# W5500_EVB_V1_0.net
KiCad netlist of a schematic drawn in EAGLE
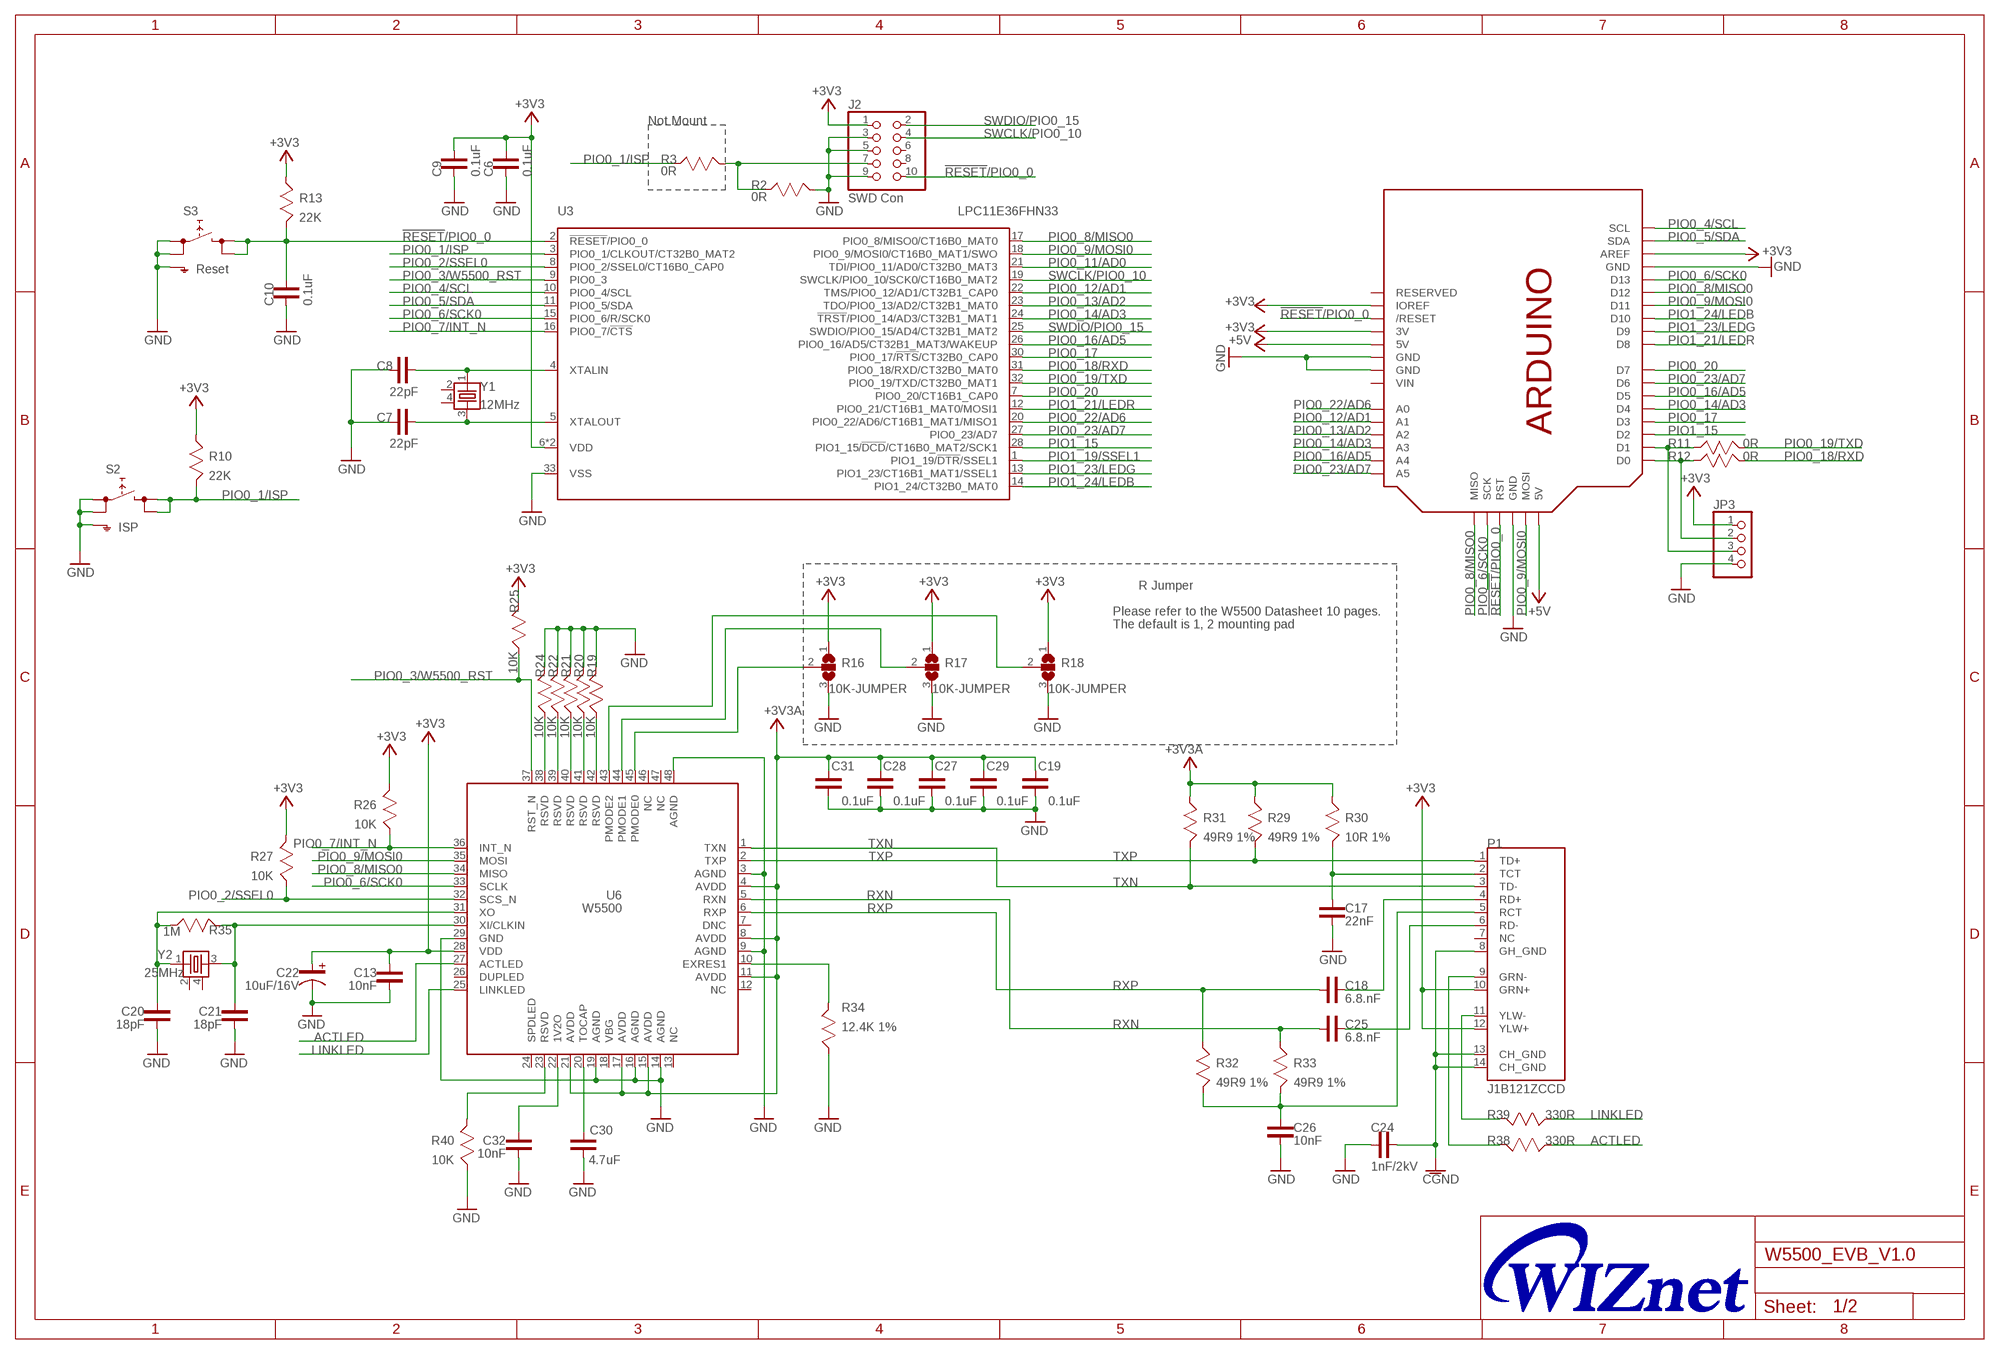
[diagram p0: schematic, sheet 1]
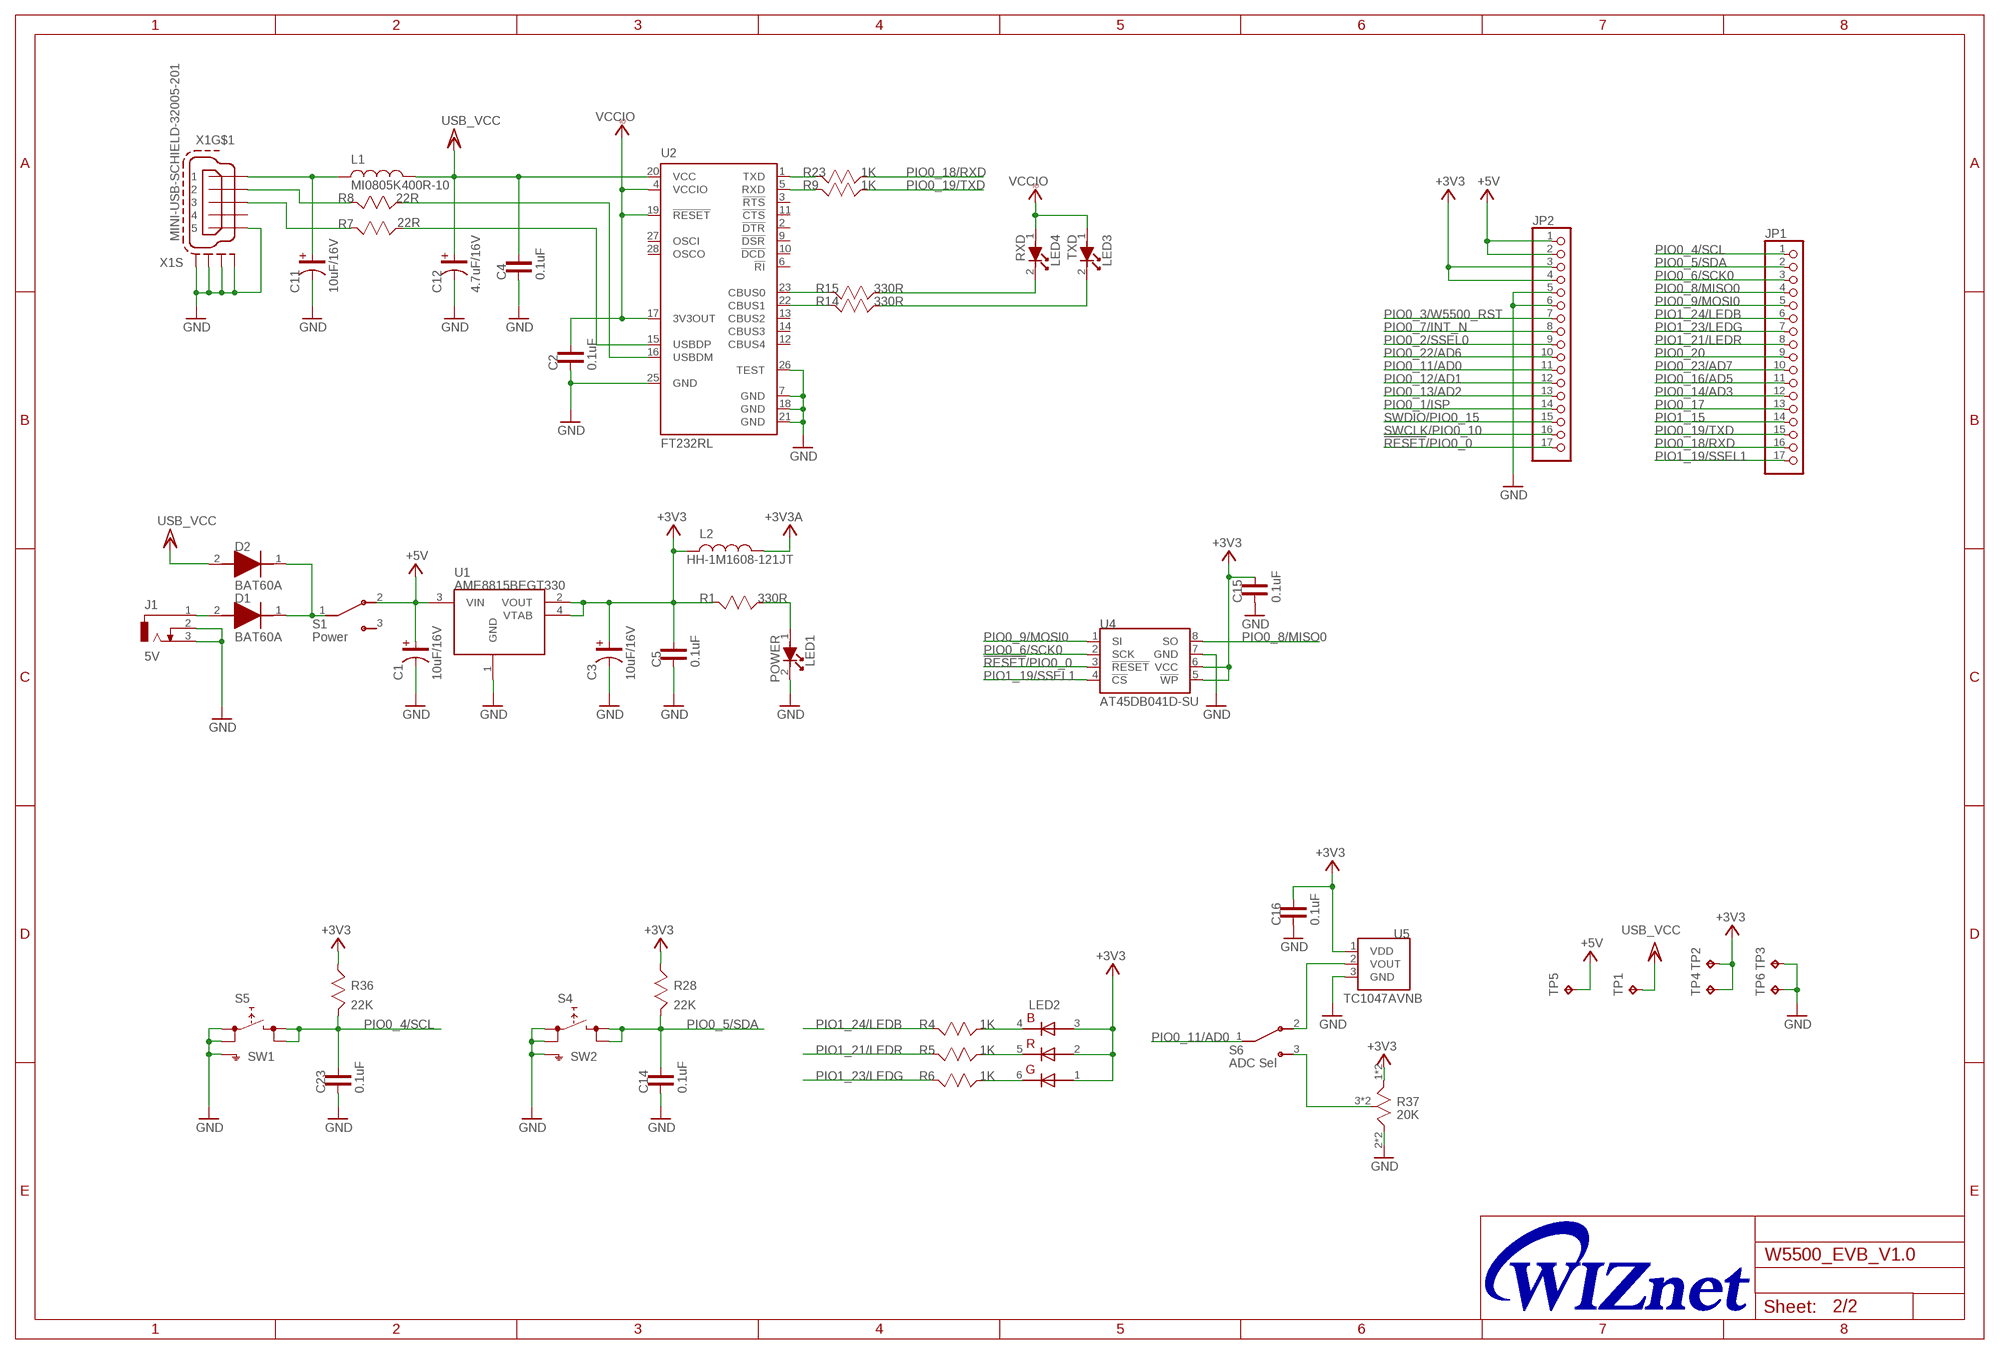
[diagram p1: schematic, sheet 2]

(export (version "E")
  (design (tool "Eeschema 10.0.6"))
  (components
    (comp (ref "$$U$3")
      (value "ARDUINO_R3_ICSP")
      (footprint "eagle-import:ARDUINOR3_ICSP")
      (libsource (lib "eagle-import") (part "ARDUINO_R3_ICSP"))
    )
    (comp (ref "C6")
      (value "0.1uF")
      (footprint "eagle-import:C-1608")
      (libsource (lib "eagle-import") (part "C-1608"))
    )
    (comp (ref "C7")
      (value "22pF")
      (footprint "eagle-import:C-1608")
      (libsource (lib "eagle-import") (part "C-1608"))
    )
    (comp (ref "C8")
      (value "22pF")
      (footprint "eagle-import:C-1608")
      (libsource (lib "eagle-import") (part "C-1608"))
    )
    (comp (ref "C9")
      (value "0.1uF")
      (footprint "eagle-import:C-1608")
      (libsource (lib "eagle-import") (part "C-1608"))
    )
    (comp (ref "C10")
      (value "0.1uF")
      (footprint "eagle-import:C-1608")
      (libsource (lib "eagle-import") (part "C-1608"))
    )
    (comp (ref "C13")
      (value "10nF")
      (footprint "eagle-import:C-1608")
      (libsource (lib "eagle-import") (part "C-1608"))
    )
    (comp (ref "C17")
      (value "22nF")
      (footprint "eagle-import:C-1608")
      (libsource (lib "eagle-import") (part "C-1608"))
    )
    (comp (ref "C18")
      (value "6.8.nF")
      (footprint "eagle-import:C-1608")
      (libsource (lib "eagle-import") (part "C-1608"))
    )
    (comp (ref "C19")
      (value "0.1uF")
      (footprint "eagle-import:C-1608")
      (libsource (lib "eagle-import") (part "C-1608"))
    )
    (comp (ref "C20")
      (value "18pF")
      (footprint "eagle-import:C-1608")
      (libsource (lib "eagle-import") (part "C-1608"))
    )
    (comp (ref "C21")
      (value "18pF")
      (footprint "eagle-import:C-1608")
      (libsource (lib "eagle-import") (part "C-1608"))
    )
    (comp (ref "C22")
      (value "10uF/16V")
      (footprint "eagle-import:C-3216(TANTAL)")
      (libsource (lib "eagle-import") (part "C-3216(TANTAL)"))
    )
    (comp (ref "C24")
      (value "1nF/2kV")
      (footprint "eagle-import:C-4520")
      (libsource (lib "eagle-import") (part "C-4520"))
    )
    (comp (ref "C25")
      (value "6.8.nF")
      (footprint "eagle-import:C-1608")
      (libsource (lib "eagle-import") (part "C-1608"))
    )
    (comp (ref "C26")
      (value "10nF")
      (footprint "eagle-import:C-1608")
      (libsource (lib "eagle-import") (part "C-1608"))
    )
    (comp (ref "C27")
      (value "0.1uF")
      (footprint "eagle-import:C-1608")
      (libsource (lib "eagle-import") (part "C-1608"))
    )
    (comp (ref "C28")
      (value "0.1uF")
      (footprint "eagle-import:C-1608")
      (libsource (lib "eagle-import") (part "C-1608"))
    )
    (comp (ref "C29")
      (value "0.1uF")
      (footprint "eagle-import:C-1608")
      (libsource (lib "eagle-import") (part "C-1608"))
    )
    (comp (ref "C30")
      (value "4.7uF")
      (footprint "eagle-import:C-2012")
      (libsource (lib "eagle-import") (part "C-2012"))
    )
    (comp (ref "C31")
      (value "0.1uF")
      (footprint "eagle-import:C-1608")
      (libsource (lib "eagle-import") (part "C-1608"))
    )
    (comp (ref "C32")
      (value "10nF")
      (footprint "eagle-import:C-1608")
      (libsource (lib "eagle-import") (part "C-1608"))
    )
    (comp (ref "J2")
      (value "SWD Con")
      (footprint "eagle-import:2X5_1.27")
      (libsource (lib "eagle-import") (part "2X5_1.27"))
    )
    (comp (ref "JP3")
      (value "PINHD-1X4")
      (footprint "eagle-import:1X04")
      (libsource (lib "eagle-import") (part "PINHD-1X4"))
    )
    (comp (ref "P1")
      (value "J1B121ZCCD")
      (footprint "eagle-import:J1B121ZCCD")
      (libsource (lib "eagle-import") (part "J1B121ZCCD"))
    )
    (comp (ref "R2")
      (value "0R")
      (footprint "eagle-import:R-1608")
      (libsource (lib "eagle-import") (part "R-1608"))
    )
    (comp (ref "R3")
      (value "0R")
      (footprint "eagle-import:R-1608")
      (libsource (lib "eagle-import") (part "R-1608"))
    )
    (comp (ref "R10")
      (value "22K")
      (footprint "eagle-import:R-1608")
      (libsource (lib "eagle-import") (part "R-1608"))
    )
    (comp (ref "R11")
      (value "0R")
      (footprint "eagle-import:R-1608")
      (libsource (lib "eagle-import") (part "R-1608"))
    )
    (comp (ref "R12")
      (value "0R")
      (footprint "eagle-import:R-1608")
      (libsource (lib "eagle-import") (part "R-1608"))
    )
    (comp (ref "R13")
      (value "22K")
      (footprint "eagle-import:R-1608")
      (libsource (lib "eagle-import") (part "R-1608"))
    )
    (comp (ref "R16")
      (value "10K-JUMPER")
      (footprint "eagle-import:R-1608-JUMPER")
      (libsource (lib "eagle-import") (part "R-1608-JUMPER"))
    )
    (comp (ref "R17")
      (value "10K-JUMPER")
      (footprint "eagle-import:R-1608-JUMPER")
      (libsource (lib "eagle-import") (part "R-1608-JUMPER"))
    )
    (comp (ref "R18")
      (value "10K-JUMPER")
      (footprint "eagle-import:R-1608-JUMPER")
      (libsource (lib "eagle-import") (part "R-1608-JUMPER"))
    )
    (comp (ref "R19")
      (value "10K")
      (footprint "eagle-import:R-1608")
      (libsource (lib "eagle-import") (part "R-1608"))
    )
    (comp (ref "R20")
      (value "10K")
      (footprint "eagle-import:R-1608")
      (libsource (lib "eagle-import") (part "R-1608"))
    )
    (comp (ref "R21")
      (value "10K")
      (footprint "eagle-import:R-1608")
      (libsource (lib "eagle-import") (part "R-1608"))
    )
    (comp (ref "R22")
      (value "10K")
      (footprint "eagle-import:R-1608")
      (libsource (lib "eagle-import") (part "R-1608"))
    )
    (comp (ref "R24")
      (value "10K")
      (footprint "eagle-import:R-1608")
      (libsource (lib "eagle-import") (part "R-1608"))
    )
    (comp (ref "R25")
      (value "10K")
      (footprint "eagle-import:R-1608")
      (libsource (lib "eagle-import") (part "R-1608"))
    )
    (comp (ref "R26")
      (value "10K")
      (footprint "eagle-import:R-1608")
      (libsource (lib "eagle-import") (part "R-1608"))
    )
    (comp (ref "R27")
      (value "10K")
      (footprint "eagle-import:R-1608")
      (libsource (lib "eagle-import") (part "R-1608"))
    )
    (comp (ref "R29")
      (value "49R9 1%")
      (footprint "eagle-import:R-1608")
      (libsource (lib "eagle-import") (part "R-1608"))
    )
    (comp (ref "R30")
      (value "10R 1%")
      (footprint "eagle-import:R-1608")
      (libsource (lib "eagle-import") (part "R-1608"))
    )
    (comp (ref "R31")
      (value "49R9 1%")
      (footprint "eagle-import:R-1608")
      (libsource (lib "eagle-import") (part "R-1608"))
    )
    (comp (ref "R32")
      (value "49R9 1%")
      (footprint "eagle-import:R-1608")
      (libsource (lib "eagle-import") (part "R-1608"))
    )
    (comp (ref "R33")
      (value "49R9 1%")
      (footprint "eagle-import:R-1608")
      (libsource (lib "eagle-import") (part "R-1608"))
    )
    (comp (ref "R34")
      (value "12.4K 1%")
      (footprint "eagle-import:R-1608")
      (libsource (lib "eagle-import") (part "R-1608"))
    )
    (comp (ref "R35")
      (value "1M")
      (footprint "eagle-import:R-1608")
      (libsource (lib "eagle-import") (part "R-1608"))
    )
    (comp (ref "R38")
      (value "330R")
      (footprint "eagle-import:R-1608")
      (libsource (lib "eagle-import") (part "R-1608"))
    )
    (comp (ref "R39")
      (value "330R")
      (footprint "eagle-import:R-1608")
      (libsource (lib "eagle-import") (part "R-1608"))
    )
    (comp (ref "R40")
      (value "10K")
      (footprint "eagle-import:R-1608")
      (libsource (lib "eagle-import") (part "R-1608"))
    )
    (comp (ref "S2")
      (value "ISP")
      (footprint "eagle-import:SKHMPXE010")
      (libsource (lib "eagle-import") (part "SKHMPE010S"))
    )
    (comp (ref "S3")
      (value "Reset")
      (footprint "eagle-import:SKHMPXE010")
      (libsource (lib "eagle-import") (part "SKHMPE010S"))
    )
    (comp (ref "U3")
      (value "LPC11E36FHN33")
      (footprint "eagle-import:SOT-HVQFN33")
      (libsource (lib "eagle-import") (part "LPC11E36FHN33"))
    )
    (comp (ref "U6")
      (value "W5500")
      (footprint "eagle-import:W5500")
      (libsource (lib "eagle-import") (part "W5500"))
    )
    (comp (ref "Y1")
      (value "12MHz")
      (footprint "eagle-import:XTAL3225")
      (libsource (lib "eagle-import") (part "XTAL3225"))
    )
    (comp (ref "Y2")
      (value "25MHz")
      (footprint "eagle-import:XTAL3225")
      (libsource (lib "eagle-import") (part "XTAL3225"))
    )
    (comp (ref "C1")
      (value "10uF/16V")
      (footprint "eagle-import:C-3216(TANTAL)")
      (libsource (lib "eagle-import") (part "C-3216(TANTAL)"))
    )
    (comp (ref "C2")
      (value "0.1uF")
      (footprint "eagle-import:C-1608")
      (libsource (lib "eagle-import") (part "C-1608"))
    )
    (comp (ref "C3")
      (value "10uF/16V")
      (footprint "eagle-import:C-3216(TANTAL)")
      (libsource (lib "eagle-import") (part "C-3216(TANTAL)"))
    )
    (comp (ref "C4")
      (value "0.1uF")
      (footprint "eagle-import:C-1608")
      (libsource (lib "eagle-import") (part "C-1608"))
    )
    (comp (ref "C5")
      (value "0.1uF")
      (footprint "eagle-import:C-1608")
      (libsource (lib "eagle-import") (part "C-1608"))
    )
    (comp (ref "C11")
      (value "10uF/16V")
      (footprint "eagle-import:C-3216(TANTAL)")
      (libsource (lib "eagle-import") (part "C-3216(TANTAL)"))
    )
    (comp (ref "C12")
      (value "4.7uF/16V")
      (footprint "eagle-import:C-3216(TANTAL)")
      (libsource (lib "eagle-import") (part "C-3216(TANTAL)"))
    )
    (comp (ref "C14")
      (value "0.1uF")
      (footprint "eagle-import:C-1608")
      (libsource (lib "eagle-import") (part "C-1608"))
    )
    (comp (ref "C15")
      (value "0.1uF")
      (footprint "eagle-import:C-1608")
      (libsource (lib "eagle-import") (part "C-1608"))
    )
    (comp (ref "C16")
      (value "0.1uF")
      (footprint "eagle-import:C-1608")
      (libsource (lib "eagle-import") (part "C-1608"))
    )
    (comp (ref "C23")
      (value "0.1uF")
      (footprint "eagle-import:C-1608")
      (libsource (lib "eagle-import") (part "C-1608"))
    )
    (comp (ref "D1")
      (value "BAT60A")
      (footprint "eagle-import:BAT60A")
      (libsource (lib "eagle-import") (part "BAT60A"))
    )
    (comp (ref "D2")
      (value "BAT60A")
      (footprint "eagle-import:BAT60A")
      (libsource (lib "eagle-import") (part "BAT60A"))
    )
    (comp (ref "J1")
      (value "5V")
      (footprint "eagle-import:DCJ0202")
      (libsource (lib "eagle-import") (part "DCJ0202"))
    )
    (comp (ref "JP1")
      (value "PINHD-1X17")
      (footprint "eagle-import:1X17")
      (libsource (lib "eagle-import") (part "PINHD-1X17"))
    )
    (comp (ref "JP2")
      (value "PINHD-1X17")
      (footprint "eagle-import:1X17")
      (libsource (lib "eagle-import") (part "PINHD-1X17"))
    )
    (comp (ref "L1")
      (value "MI0805K400R-10")
      (footprint "eagle-import:L-2012")
      (libsource (lib "eagle-import") (part "L-2012"))
    )
    (comp (ref "L2")
      (value "HH-1M1608-121JT")
      (footprint "eagle-import:L-1608")
      (libsource (lib "eagle-import") (part "L-1608"))
    )
    (comp (ref "LED1")
      (value "POWER")
      (footprint "eagle-import:LED-1608")
      (libsource (lib "eagle-import") (part "LED-1608"))
    )
    (comp (ref "LED2")
      (value "LS5050RGB5050")
      (footprint "eagle-import:LS5050RGB")
      (libsource (lib "eagle-import") (part "LS5050RGB5050"))
    )
    (comp (ref "LED3")
      (value "TXD")
      (footprint "eagle-import:LED-1608")
      (libsource (lib "eagle-import") (part "LED-1608"))
    )
    (comp (ref "LED4")
      (value "RXD")
      (footprint "eagle-import:LED-1608")
      (libsource (lib "eagle-import") (part "LED-1608"))
    )
    (comp (ref "R1")
      (value "330R")
      (footprint "eagle-import:R-1608")
      (libsource (lib "eagle-import") (part "R-1608"))
    )
    (comp (ref "R4")
      (value "1K")
      (footprint "eagle-import:R-1608")
      (libsource (lib "eagle-import") (part "R-1608"))
    )
    (comp (ref "R5")
      (value "1K")
      (footprint "eagle-import:R-1608")
      (libsource (lib "eagle-import") (part "R-1608"))
    )
    (comp (ref "R6")
      (value "1K")
      (footprint "eagle-import:R-1608")
      (libsource (lib "eagle-import") (part "R-1608"))
    )
    (comp (ref "R7")
      (value "22R")
      (footprint "eagle-import:R-1608")
      (libsource (lib "eagle-import") (part "R-1608"))
    )
    (comp (ref "R8")
      (value "22R")
      (footprint "eagle-import:R-1608")
      (libsource (lib "eagle-import") (part "R-1608"))
    )
    (comp (ref "R9")
      (value "1K")
      (footprint "eagle-import:R-1608")
      (libsource (lib "eagle-import") (part "R-1608"))
    )
    (comp (ref "R14")
      (value "330R")
      (footprint "eagle-import:R-1608")
      (libsource (lib "eagle-import") (part "R-1608"))
    )
    (comp (ref "R15")
      (value "330R")
      (footprint "eagle-import:R-1608")
      (libsource (lib "eagle-import") (part "R-1608"))
    )
    (comp (ref "R23")
      (value "1K")
      (footprint "eagle-import:R-1608")
      (libsource (lib "eagle-import") (part "R-1608"))
    )
    (comp (ref "R28")
      (value "22K")
      (footprint "eagle-import:R-1608")
      (libsource (lib "eagle-import") (part "R-1608"))
    )
    (comp (ref "R36")
      (value "22K")
      (footprint "eagle-import:R-1608")
      (libsource (lib "eagle-import") (part "R-1608"))
    )
    (comp (ref "R37")
      (value "20K")
      (footprint "eagle-import:RES-VAR-PT10(DUAL)")
      (libsource (lib "eagle-import") (part "RES-VAR-PT10DAUL"))
    )
    (comp (ref "S1")
      (value "Power")
      (footprint "eagle-import:IMMS-12H")
      (libsource (lib "eagle-import") (part "IMMS-12H"))
    )
    (comp (ref "S4")
      (value "SW2")
      (footprint "eagle-import:SKHMPXE010")
      (libsource (lib "eagle-import") (part "SKHMPE010S"))
    )
    (comp (ref "S5")
      (value "SW1")
      (footprint "eagle-import:SKHMPXE010")
      (libsource (lib "eagle-import") (part "SKHMPE010S"))
    )
    (comp (ref "S6")
      (value "ADC Sel")
      (footprint "eagle-import:IMMS-12H")
      (libsource (lib "eagle-import") (part "IMMS-12H"))
    )
    (comp (ref "TP1")
      (value "TPB1,27")
      (footprint "eagle-import:B1,27")
      (libsource (lib "eagle-import") (part "TPB1,27"))
    )
    (comp (ref "TP2")
      (value "TPB1,27")
      (footprint "eagle-import:B1,27")
      (libsource (lib "eagle-import") (part "TPB1,27"))
    )
    (comp (ref "TP3")
      (value "TPB1,27")
      (footprint "eagle-import:B1,27")
      (libsource (lib "eagle-import") (part "TPB1,27"))
    )
    (comp (ref "TP4")
      (value "TPB1,27")
      (footprint "eagle-import:B1,27")
      (libsource (lib "eagle-import") (part "TPB1,27"))
    )
    (comp (ref "TP5")
      (value "TPB1,27")
      (footprint "eagle-import:B1,27")
      (libsource (lib "eagle-import") (part "TPB1,27"))
    )
    (comp (ref "TP6")
      (value "TPB1,27")
      (footprint "eagle-import:B1,27")
      (libsource (lib "eagle-import") (part "TPB1,27"))
    )
    (comp (ref "U1")
      (value "AME8815BEGT330")
      (footprint "eagle-import:SOT-223")
      (libsource (lib "eagle-import") (part "AME8815BEGT330"))
    )
    (comp (ref "U2")
      (value "FT232RL")
      (footprint "eagle-import:SSOP28")
      (libsource (lib "eagle-import") (part "FT232RL"))
    )
    (comp (ref "U4")
      (value "AT45DB041D-SU")
      (footprint "eagle-import:8S2")
      (libsource (lib "eagle-import") (part "AT45DB041D-SU"))
    )
    (comp (ref "U5")
      (value "TC1047AVNB")
      (footprint "eagle-import:SOT23")
      (libsource (lib "eagle-import") (part "TC1047AVNB"))
    )
    (comp (ref "X1")
      (value "MINI-USB-SCHIELD-32005-201")
      (footprint "eagle-import:32005-201")
      (libsource (lib "eagle-import") (part "MINI-USB-SCHIELD-32005-201"))
    )
  )
  (nets
    (net (code "1") (name "+3V3") (class "Default")
      (node (ref "$$U$3") (pin "3V") (pinfunction "3V_3V") (pintype "power_in"))
      (node (ref "$$U$3") (pin "AREF") (pinfunction "AREF_AREF") (pintype "bidirectional"))
      (node (ref "$$U$3") (pin "IOREF") (pinfunction "IOREF_IOREF") (pintype "output"))
      (node (ref "C13") (pin "2") (pinfunction "P$2_2") (pintype "passive"))
      (node (ref "C15") (pin "2") (pinfunction "P$2_2") (pintype "passive"))
      (node (ref "C16") (pin "2") (pinfunction "P$2_2") (pintype "passive"))
      (node (ref "C22") (pin "1") (pinfunction "1_1") (pintype "passive"))
      (node (ref "C3") (pin "1") (pinfunction "1_1") (pintype "passive"))
      (node (ref "C5") (pin "2") (pinfunction "P$2_2") (pintype "passive"))
      (node (ref "C6") (pin "2") (pinfunction "P$2_2") (pintype "passive"))
      (node (ref "C9") (pin "2") (pinfunction "P$2_2") (pintype "passive"))
      (node (ref "J2") (pin "1") (pinfunction "1_1") (pintype "passive"))
      (node (ref "JP2") (pin "3") (pinfunction "3_3") (pintype "passive"))
      (node (ref "JP2") (pin "4") (pinfunction "4_4") (pintype "passive"))
      (node (ref "JP3") (pin "1") (pinfunction "1_1") (pintype "passive"))
      (node (ref "L2") (pin "1") (pinfunction "1_1") (pintype "passive"))
      (node (ref "LED2") (pin "1") (pinfunction "GREEN_A_1") (pintype "bidirectional"))
      (node (ref "LED2") (pin "2") (pinfunction "RED_A_2") (pintype "bidirectional"))
      (node (ref "LED2") (pin "3") (pinfunction "BLUE_A_3") (pintype "bidirectional"))
      (node (ref "P1") (pin "10") (pinfunction "GRN+_10") (pintype "passive"))
      (node (ref "P1") (pin "12") (pinfunction "YLW+_12") (pintype "passive"))
      (node (ref "R1") (pin "1") (pinfunction "P$1_1") (pintype "passive"))
      (node (ref "R10") (pin "2") (pinfunction "P$2_2") (pintype "passive"))
      (node (ref "R13") (pin "2") (pinfunction "P$2_2") (pintype "passive"))
      (node (ref "R16") (pin "1") (pinfunction "1_1") (pintype "passive"))
      (node (ref "R17") (pin "1") (pinfunction "1_1") (pintype "passive"))
      (node (ref "R18") (pin "1") (pinfunction "1_1") (pintype "passive"))
      (node (ref "R25") (pin "2") (pinfunction "P$2_2") (pintype "passive"))
      (node (ref "R26") (pin "2") (pinfunction "P$2_2") (pintype "passive"))
      (node (ref "R27") (pin "2") (pinfunction "P$2_2") (pintype "passive"))
      (node (ref "R28") (pin "2") (pinfunction "P$2_2") (pintype "passive"))
      (node (ref "R36") (pin "2") (pinfunction "P$2_2") (pintype "passive"))
      (node (ref "R37") (pin "1") (pinfunction "P$1_1") (pintype "passive"))
      (node (ref "R37") (pin "P$1") (pinfunction "P$1_P$1") (pintype "passive"))
      (node (ref "TP2") (pin "TP") (pinfunction "TP_TP") (pintype "input"))
      (node (ref "TP4") (pin "TP") (pinfunction "TP_TP") (pintype "input"))
      (node (ref "U1") (pin "2") (pinfunction "VOUT_2") (pintype "passive"))
      (node (ref "U1") (pin "4") (pinfunction "VTAB_4") (pintype "passive"))
      (node (ref "U3") (pin "29") (pinfunction "VDD_29") (pintype "power_in"))
      (node (ref "U3") (pin "6") (pinfunction "VDD_6") (pintype "power_in"))
      (node (ref "U4") (pin "5") (pinfunction "~{WP}_5") (pintype "passive"))
      (node (ref "U4") (pin "6") (pinfunction "VCC_6") (pintype "passive"))
      (node (ref "U5") (pin "1") (pinfunction "VDD_1") (pintype "passive"))
      (node (ref "U6") (pin "28") (pinfunction "VDD_28") (pintype "passive"))
    )
    (net (code "2") (name "+3V3A") (class "Default")
      (node (ref "C19") (pin "2") (pinfunction "P$2_2") (pintype "passive"))
      (node (ref "C27") (pin "2") (pinfunction "P$2_2") (pintype "passive"))
      (node (ref "C28") (pin "2") (pinfunction "P$2_2") (pintype "passive"))
      (node (ref "C29") (pin "2") (pinfunction "P$2_2") (pintype "passive"))
      (node (ref "C31") (pin "2") (pinfunction "P$2_2") (pintype "passive"))
      (node (ref "L2") (pin "P$2") (pinfunction "2_P$2") (pintype "passive"))
      (node (ref "R29") (pin "2") (pinfunction "P$2_2") (pintype "passive"))
      (node (ref "R30") (pin "2") (pinfunction "P$2_2") (pintype "passive"))
      (node (ref "R31") (pin "2") (pinfunction "P$2_2") (pintype "passive"))
      (node (ref "U6") (pin "11") (pinfunction "AVDD_11") (pintype "passive"))
      (node (ref "U6") (pin "15") (pinfunction "AVDD_15") (pintype "passive"))
      (node (ref "U6") (pin "17") (pinfunction "AVDD_17") (pintype "passive"))
      (node (ref "U6") (pin "21") (pinfunction "AVDD_21") (pintype "passive"))
      (node (ref "U6") (pin "4") (pinfunction "AVDD_4") (pintype "passive"))
      (node (ref "U6") (pin "8") (pinfunction "AVDD_8") (pintype "passive"))
    )
    (net (code "3") (name "+5V") (class "Default")
      (node (ref "$$U$3") (pin "5V") (pinfunction "5V_5V") (pintype "power_in"))
      (node (ref "$$U$3") (pin "5V_ICSP") (pinfunction "5V_5V_ICSP") (pintype "passive"))
      (node (ref "C1") (pin "1") (pinfunction "1_1") (pintype "passive"))
      (node (ref "JP2") (pin "1") (pinfunction "1_1") (pintype "passive"))
      (node (ref "JP2") (pin "2") (pinfunction "2_2") (pintype "passive"))
      (node (ref "S1") (pin "2") (pinfunction "2_2") (pintype "passive"))
      (node (ref "TP5") (pin "TP") (pinfunction "TP_TP") (pintype "input"))
      (node (ref "U1") (pin "3") (pinfunction "VIN_3") (pintype "passive"))
    )
    (net (code "4") (name "ACTLED") (class "Default")
      (node (ref "R38") (pin "2") (pinfunction "P$2_2") (pintype "passive"))
      (node (ref "U6") (pin "27") (pinfunction "ACTLED_27") (pintype "passive"))
    )
    (net (code "5") (name "CGND") (class "Default")
      (node (ref "C24") (pin "2") (pinfunction "P$2_2") (pintype "passive"))
      (node (ref "P1") (pin "13") (pinfunction "CH_GND_13") (pintype "passive"))
      (node (ref "P1") (pin "14") (pinfunction "CH_GND_14") (pintype "passive"))
      (node (ref "P1") (pin "8") (pinfunction "GH_GND_8") (pintype "passive"))
    )
    (net (code "6") (name "GND") (class "Default")
      (node (ref "$$U$3") (pin "GND") (pinfunction "GND_GND") (pintype "power_in"))
      (node (ref "$$U$3") (pin "GND@1") (pinfunction "GND_GND@1") (pintype "power_in"))
      (node (ref "$$U$3") (pin "GND@2") (pinfunction "GND_GND@2") (pintype "passive"))
      (node (ref "$$U$3") (pin "GND@3") (pinfunction "GND_GND@3") (pintype "power_in"))
      (node (ref "C1") (pin "2") (pinfunction "2_2") (pintype "passive"))
      (node (ref "C10") (pin "1") (pinfunction "P$1_1") (pintype "passive"))
      (node (ref "C11") (pin "2") (pinfunction "2_2") (pintype "passive"))
      (node (ref "C12") (pin "2") (pinfunction "2_2") (pintype "passive"))
      (node (ref "C13") (pin "1") (pinfunction "P$1_1") (pintype "passive"))
      (node (ref "C14") (pin "1") (pinfunction "P$1_1") (pintype "passive"))
      (node (ref "C15") (pin "1") (pinfunction "P$1_1") (pintype "passive"))
      (node (ref "C16") (pin "1") (pinfunction "P$1_1") (pintype "passive"))
      (node (ref "C17") (pin "1") (pinfunction "P$1_1") (pintype "passive"))
      (node (ref "C19") (pin "1") (pinfunction "P$1_1") (pintype "passive"))
      (node (ref "C2") (pin "1") (pinfunction "P$1_1") (pintype "passive"))
      (node (ref "C20") (pin "1") (pinfunction "P$1_1") (pintype "passive"))
      (node (ref "C21") (pin "1") (pinfunction "P$1_1") (pintype "passive"))
      (node (ref "C22") (pin "2") (pinfunction "2_2") (pintype "passive"))
      (node (ref "C23") (pin "1") (pinfunction "P$1_1") (pintype "passive"))
      (node (ref "C24") (pin "1") (pinfunction "P$1_1") (pintype "passive"))
      (node (ref "C26") (pin "1") (pinfunction "P$1_1") (pintype "passive"))
      (node (ref "C27") (pin "1") (pinfunction "P$1_1") (pintype "passive"))
      (node (ref "C28") (pin "1") (pinfunction "P$1_1") (pintype "passive"))
      (node (ref "C29") (pin "1") (pinfunction "P$1_1") (pintype "passive"))
      (node (ref "C3") (pin "2") (pinfunction "2_2") (pintype "passive"))
      (node (ref "C30") (pin "P$1") (pinfunction "P$1_P$1") (pintype "passive"))
      (node (ref "C31") (pin "1") (pinfunction "P$1_1") (pintype "passive"))
      (node (ref "C32") (pin "1") (pinfunction "P$1_1") (pintype "passive"))
      (node (ref "C4") (pin "1") (pinfunction "P$1_1") (pintype "passive"))
      (node (ref "C5") (pin "1") (pinfunction "P$1_1") (pintype "passive"))
      (node (ref "C6") (pin "1") (pinfunction "P$1_1") (pintype "passive"))
      (node (ref "C7") (pin "1") (pinfunction "P$1_1") (pintype "passive"))
      (node (ref "C8") (pin "1") (pinfunction "P$1_1") (pintype "passive"))
      (node (ref "C9") (pin "1") (pinfunction "P$1_1") (pintype "passive"))
      (node (ref "J1") (pin "2") (pinfunction "2_2") (pintype "passive"))
      (node (ref "J1") (pin "3") (pinfunction "3_3") (pintype "passive"))
      (node (ref "J2") (pin "3") (pinfunction "3_3") (pintype "passive"))
      (node (ref "J2") (pin "5") (pinfunction "5_5") (pintype "passive"))
      (node (ref "J2") (pin "9") (pinfunction "9_9") (pintype "passive"))
      (node (ref "JP2") (pin "5") (pinfunction "5_5") (pintype "passive"))
      (node (ref "JP2") (pin "6") (pinfunction "6_6") (pintype "passive"))
      (node (ref "JP3") (pin "4") (pinfunction "4_4") (pintype "passive"))
      (node (ref "LED1") (pin "2") (pinfunction "P$2_2") (pintype "bidirectional"))
      (node (ref "R16") (pin "3") (pinfunction "3_3") (pintype "passive"))
      (node (ref "R17") (pin "3") (pinfunction "3_3") (pintype "passive"))
      (node (ref "R18") (pin "3") (pinfunction "3_3") (pintype "passive"))
      (node (ref "R19") (pin "2") (pinfunction "P$2_2") (pintype "passive"))
      (node (ref "R2") (pin "1") (pinfunction "P$1_1") (pintype "passive"))
      (node (ref "R20") (pin "2") (pinfunction "P$2_2") (pintype "passive"))
      (node (ref "R21") (pin "2") (pinfunction "P$2_2") (pintype "passive"))
      (node (ref "R22") (pin "2") (pinfunction "P$2_2") (pintype "passive"))
      (node (ref "R24") (pin "2") (pinfunction "P$2_2") (pintype "passive"))
      (node (ref "R34") (pin "1") (pinfunction "P$1_1") (pintype "passive"))
      (node (ref "R37") (pin "2") (pinfunction "P$2_2") (pintype "passive"))
      (node (ref "R37") (pin "P$3") (pinfunction "P$2_P$3") (pintype "passive"))
      (node (ref "R40") (pin "1") (pinfunction "P$1_1") (pintype "passive"))
      (node (ref "S2") (pin "1") (pinfunction "1.1_1") (pintype "passive"))
      (node (ref "S2") (pin "2") (pinfunction "1.2_2") (pintype "passive"))
      (node (ref "S2") (pin "5") (pinfunction "SH_5") (pintype "passive"))
      (node (ref "S3") (pin "1") (pinfunction "1.1_1") (pintype "passive"))
      (node (ref "S3") (pin "2") (pinfunction "1.2_2") (pintype "passive"))
      (node (ref "S3") (pin "5") (pinfunction "SH_5") (pintype "passive"))
      (node (ref "S4") (pin "1") (pinfunction "1.1_1") (pintype "passive"))
      (node (ref "S4") (pin "2") (pinfunction "1.2_2") (pintype "passive"))
      (node (ref "S4") (pin "5") (pinfunction "SH_5") (pintype "passive"))
      (node (ref "S5") (pin "1") (pinfunction "1.1_1") (pintype "passive"))
      (node (ref "S5") (pin "2") (pinfunction "1.2_2") (pintype "passive"))
      (node (ref "S5") (pin "5") (pinfunction "SH_5") (pintype "passive"))
      (node (ref "TP3") (pin "TP") (pinfunction "TP_TP") (pintype "input"))
      (node (ref "TP6") (pin "TP") (pinfunction "TP_TP") (pintype "input"))
      (node (ref "U1") (pin "1") (pinfunction "GND_1") (pintype "passive"))
      (node (ref "U2") (pin "18") (pinfunction "GND_18") (pintype "power_in"))
      (node (ref "U2") (pin "21") (pinfunction "GND_21") (pintype "power_in"))
      (node (ref "U2") (pin "25") (pinfunction "GND_25") (pintype "power_in"))
      (node (ref "U2") (pin "26") (pinfunction "TEST_26") (pintype "input"))
      (node (ref "U2") (pin "7") (pinfunction "GND_7") (pintype "power_in"))
      (node (ref "U3") (pin "33") (pinfunction "VSS_33") (pintype "power_in"))
      (node (ref "U4") (pin "7") (pinfunction "GND_7") (pintype "passive"))
      (node (ref "U5") (pin "3") (pinfunction "GND_3") (pintype "passive"))
      (node (ref "U6") (pin "14") (pinfunction "AGND_14") (pintype "passive"))
      (node (ref "U6") (pin "16") (pinfunction "AGND_16") (pintype "passive"))
      (node (ref "U6") (pin "19") (pinfunction "AGND_19") (pintype "passive"))
      (node (ref "U6") (pin "29") (pinfunction "GND_29") (pintype "passive"))
      (node (ref "U6") (pin "3") (pinfunction "AGND_3") (pintype "passive"))
      (node (ref "U6") (pin "48") (pinfunction "AGND_48") (pintype "passive"))
      (node (ref "U6") (pin "9") (pinfunction "AGND_9") (pintype "passive"))
      (node (ref "X1") (pin "5") (pinfunction "5_5") (pintype "passive"))
      (node (ref "X1") (pin "M1") (pinfunction "S1_M1") (pintype "passive"))
      (node (ref "X1") (pin "M2") (pinfunction "S2_M2") (pintype "passive"))
      (node (ref "X1") (pin "M3") (pinfunction "S3_M3") (pintype "passive"))
      (node (ref "X1") (pin "M4") (pinfunction "S4_M4") (pintype "passive"))
    )
    (net (code "7") (name "LINKLED") (class "Default")
      (node (ref "R39") (pin "2") (pinfunction "P$2_2") (pintype "passive"))
      (node (ref "U6") (pin "25") (pinfunction "LINKLED_25") (pintype "passive"))
    )
    (net (code "8") (name "Net-(C7-P$2)") (class "Default")
      (node (ref "C7") (pin "2") (pinfunction "P$2_2") (pintype "passive"))
      (node (ref "U3") (pin "5") (pinfunction "XTALOUT_5") (pintype "output"))
      (node (ref "Y1") (pin "3") (pinfunction "3_3") (pintype "passive"))
    )
    (net (code "9") (name "Net-(C8-P$2)") (class "Default")
      (node (ref "C8") (pin "2") (pinfunction "P$2_2") (pintype "passive"))
      (node (ref "U3") (pin "4") (pinfunction "XTALIN_4") (pintype "input"))
      (node (ref "Y1") (pin "1") (pinfunction "1_1") (pintype "passive"))
    )
    (net (code "10") (name "Net-(C11-Pad1)") (class "Default")
      (node (ref "C11") (pin "1") (pinfunction "1_1") (pintype "passive"))
      (node (ref "L1") (pin "1") (pinfunction "1_1") (pintype "passive"))
      (node (ref "X1") (pin "1") (pinfunction "1_1") (pintype "passive"))
    )
    (net (code "11") (name "Net-(C17-P$2)") (class "Default")
      (node (ref "C17") (pin "2") (pinfunction "P$2_2") (pintype "passive"))
      (node (ref "P1") (pin "2") (pinfunction "TCT_2") (pintype "passive"))
      (node (ref "R30") (pin "1") (pinfunction "P$1_1") (pintype "passive"))
    )
    (net (code "12") (name "Net-(C18-P$1)") (class "Default")
      (node (ref "C18") (pin "1") (pinfunction "P$1_1") (pintype "passive"))
      (node (ref "P1") (pin "4") (pinfunction "RD+_4") (pintype "passive"))
    )
    (net (code "13") (name "Net-(C20-P$2)") (class "Default")
      (node (ref "C20") (pin "2") (pinfunction "P$2_2") (pintype "passive"))
      (node (ref "R35") (pin "1") (pinfunction "P$1_1") (pintype "passive"))
      (node (ref "U6") (pin "31") (pinfunction "XO_31") (pintype "passive"))
      (node (ref "Y2") (pin "1") (pinfunction "1_1") (pintype "passive"))
    )
    (net (code "14") (name "Net-(C21-P$2)") (class "Default")
      (node (ref "C21") (pin "2") (pinfunction "P$2_2") (pintype "passive"))
      (node (ref "R35") (pin "2") (pinfunction "P$2_2") (pintype "passive"))
      (node (ref "U6") (pin "30") (pinfunction "XI/CLKIN_30") (pintype "passive"))
      (node (ref "Y2") (pin "3") (pinfunction "3_3") (pintype "passive"))
    )
    (net (code "15") (name "Net-(C25-P$1)") (class "Default")
      (node (ref "C25") (pin "1") (pinfunction "P$1_1") (pintype "passive"))
      (node (ref "P1") (pin "6") (pinfunction "RD-_6") (pintype "passive"))
    )
    (net (code "16") (name "Net-(C26-P$2)") (class "Default")
      (node (ref "C26") (pin "2") (pinfunction "P$2_2") (pintype "passive"))
      (node (ref "P1") (pin "5") (pinfunction "RCT_5") (pintype "passive"))
      (node (ref "R32") (pin "1") (pinfunction "P$1_1") (pintype "passive"))
      (node (ref "R33") (pin "1") (pinfunction "P$1_1") (pintype "passive"))
    )
    (net (code "17") (name "Net-(C32-P$2)") (class "Default")
      (node (ref "C32") (pin "2") (pinfunction "P$2_2") (pintype "passive"))
      (node (ref "U6") (pin "22") (pinfunction "1V2O_22") (pintype "passive"))
    )
    (net (code "18") (name "Net-(D1-Pad1)") (class "Default")
      (node (ref "D1") (pin "1") (pinfunction "1_1") (pintype "bidirectional"))
      (node (ref "D2") (pin "1") (pinfunction "1_1") (pintype "bidirectional"))
      (node (ref "S1") (pin "1") (pinfunction "1_1") (pintype "passive"))
    )
    (net (code "19") (name "Net-(D1-Pad2)") (class "Default")
      (node (ref "D1") (pin "2") (pinfunction "2_2") (pintype "bidirectional"))
      (node (ref "J1") (pin "1") (pinfunction "1_1") (pintype "passive"))
    )
    (net (code "20") (name "Net-(LED1-P$1)") (class "Default")
      (node (ref "LED1") (pin "1") (pinfunction "P$1_1") (pintype "bidirectional"))
      (node (ref "R1") (pin "2") (pinfunction "P$2_2") (pintype "passive"))
    )
    (net (code "21") (name "Net-(LED2-BLUE_C)") (class "Default")
      (node (ref "LED2") (pin "4") (pinfunction "BLUE_C_4") (pintype "bidirectional"))
      (node (ref "R4") (pin "2") (pinfunction "P$2_2") (pintype "passive"))
    )
    (net (code "22") (name "Net-(LED2-GREEN_C)") (class "Default")
      (node (ref "LED2") (pin "6") (pinfunction "GREEN_C_6") (pintype "bidirectional"))
      (node (ref "R6") (pin "2") (pinfunction "P$2_2") (pintype "passive"))
    )
    (net (code "23") (name "Net-(LED2-RED_C)") (class "Default")
      (node (ref "LED2") (pin "5") (pinfunction "RED_C_5") (pintype "bidirectional"))
      (node (ref "R5") (pin "2") (pinfunction "P$2_2") (pintype "passive"))
    )
    (net (code "24") (name "Net-(LED3-P$2)") (class "Default")
      (node (ref "LED3") (pin "2") (pinfunction "P$2_2") (pintype "bidirectional"))
      (node (ref "R14") (pin "2") (pinfunction "P$2_2") (pintype "passive"))
    )
    (net (code "25") (name "Net-(LED4-P$2)") (class "Default")
      (node (ref "LED4") (pin "2") (pinfunction "P$2_2") (pintype "bidirectional"))
      (node (ref "R15") (pin "2") (pinfunction "P$2_2") (pintype "passive"))
    )
    (net (code "26") (name "Net-(P1-GRN-)") (class "Default")
      (node (ref "P1") (pin "9") (pinfunction "GRN-_9") (pintype "passive"))
      (node (ref "R38") (pin "1") (pinfunction "P$1_1") (pintype "passive"))
    )
    (net (code "27") (name "Net-(P1-YLW-)") (class "Default")
      (node (ref "P1") (pin "11") (pinfunction "YLW-_11") (pintype "passive"))
      (node (ref "R39") (pin "1") (pinfunction "P$1_1") (pintype "passive"))
    )
    (net (code "28") (name "Net-(R2-P$2)") (class "Default")
      (node (ref "J2") (pin "7") (pinfunction "7_7") (pintype "passive"))
      (node (ref "R2") (pin "2") (pinfunction "P$2_2") (pintype "passive"))
      (node (ref "R3") (pin "1") (pinfunction "P$1_1") (pintype "passive"))
    )
    (net (code "29") (name "Net-(R7-P$1)") (class "Default")
      (node (ref "R7") (pin "1") (pinfunction "P$1_1") (pintype "passive"))
      (node (ref "X1") (pin "3") (pinfunction "3_3") (pintype "passive"))
    )
    (net (code "30") (name "Net-(R7-P$2)") (class "Default")
      (node (ref "R7") (pin "2") (pinfunction "P$2_2") (pintype "passive"))
      (node (ref "U2") (pin "15") (pinfunction "USBDP_15") (pintype "bidirectional"))
    )
    (net (code "31") (name "Net-(R8-P$1)") (class "Default")
      (node (ref "R8") (pin "1") (pinfunction "P$1_1") (pintype "passive"))
      (node (ref "X1") (pin "2") (pinfunction "2_2") (pintype "passive"))
    )
    (net (code "32") (name "Net-(R8-P$2)") (class "Default")
      (node (ref "R8") (pin "2") (pinfunction "P$2_2") (pintype "passive"))
      (node (ref "U2") (pin "16") (pinfunction "USBDM_16") (pintype "bidirectional"))
    )
    (net (code "33") (name "Net-(R9-P$1)") (class "Default")
      (node (ref "R9") (pin "1") (pinfunction "P$1_1") (pintype "passive"))
      (node (ref "U2") (pin "5") (pinfunction "RXD_5") (pintype "input"))
    )
    (net (code "34") (name "Net-(R11-P$2)") (class "Default")
      (node (ref "$$U$3") (pin "D1") (pinfunction "D1_D1") (pintype "bidirectional"))
      (node (ref "JP3") (pin "3") (pinfunction "3_3") (pintype "passive"))
      (node (ref "R11") (pin "2") (pinfunction "P$2_2") (pintype "passive"))
    )
    (net (code "35") (name "Net-(R12-P$2)") (class "Default")
      (node (ref "$$U$3") (pin "D0") (pinfunction "D0_D0") (pintype "bidirectional"))
      (node (ref "JP3") (pin "2") (pinfunction "2_2") (pintype "passive"))
      (node (ref "R12") (pin "2") (pinfunction "P$2_2") (pintype "passive"))
    )
    (net (code "36") (name "Net-(R14-P$1)") (class "Default")
      (node (ref "R14") (pin "1") (pinfunction "P$1_1") (pintype "passive"))
      (node (ref "U2") (pin "22") (pinfunction "CBUS1_22") (pintype "bidirectional"))
    )
    (net (code "37") (name "Net-(R15-P$1)") (class "Default")
      (node (ref "R15") (pin "1") (pinfunction "P$1_1") (pintype "passive"))
      (node (ref "U2") (pin "23") (pinfunction "CBUS0_23") (pintype "bidirectional"))
    )
    (net (code "38") (name "Net-(R19-P$1)") (class "Default")
      (node (ref "R19") (pin "1") (pinfunction "P$1_1") (pintype "passive"))
      (node (ref "U6") (pin "42") (pinfunction "RSVD_42") (pintype "passive"))
    )
    (net (code "39") (name "Net-(R20-P$1)") (class "Default")
      (node (ref "R20") (pin "1") (pinfunction "P$1_1") (pintype "passive"))
      (node (ref "U6") (pin "41") (pinfunction "RSVD_41") (pintype "passive"))
    )
    (net (code "40") (name "Net-(R21-P$1)") (class "Default")
      (node (ref "R21") (pin "1") (pinfunction "P$1_1") (pintype "passive"))
      (node (ref "U6") (pin "40") (pinfunction "RSVD_40") (pintype "passive"))
    )
    (net (code "41") (name "Net-(R22-P$1)") (class "Default")
      (node (ref "R22") (pin "1") (pinfunction "P$1_1") (pintype "passive"))
      (node (ref "U6") (pin "39") (pinfunction "RSVD_39") (pintype "passive"))
    )
    (net (code "42") (name "Net-(R23-P$1)") (class "Default")
      (node (ref "R23") (pin "1") (pinfunction "P$1_1") (pintype "passive"))
      (node (ref "U2") (pin "1") (pinfunction "TXD_1") (pintype "output"))
    )
    (net (code "43") (name "Net-(R24-P$1)") (class "Default")
      (node (ref "R24") (pin "1") (pinfunction "P$1_1") (pintype "passive"))
      (node (ref "U6") (pin "38") (pinfunction "RSVD_38") (pintype "passive"))
    )
    (net (code "44") (name "Net-(R34-P$2)") (class "Default")
      (node (ref "R34") (pin "2") (pinfunction "P$2_2") (pintype "passive"))
      (node (ref "U6") (pin "10") (pinfunction "EXRES1_10") (pintype "passive"))
    )
    (net (code "45") (name "Net-(R37-P$3-Pad3)") (class "Default")
      (node (ref "R37") (pin "3") (pinfunction "P$3_3") (pintype "passive"))
      (node (ref "R37") (pin "P$2") (pinfunction "P$3_P$2") (pintype "passive"))
      (node (ref "S6") (pin "3") (pinfunction "3_3") (pintype "passive"))
    )
    (net (code "46") (name "Net-(R40-P$2)") (class "Default")
      (node (ref "R40") (pin "2") (pinfunction "P$2_2") (pintype "passive"))
      (node (ref "U6") (pin "23") (pinfunction "RSVD_23") (pintype "passive"))
    )
    (net (code "47") (name "Net-(U5-VOUT)") (class "Default")
      (node (ref "S6") (pin "2") (pinfunction "2_2") (pintype "passive"))
      (node (ref "U5") (pin "2") (pinfunction "VOUT_2") (pintype "passive"))
    )
    (net (code "48") (name "Net-(U6-PMODE0)") (class "Default")
      (node (ref "R16") (pin "2") (pinfunction "2_2") (pintype "passive"))
      (node (ref "U6") (pin "45") (pinfunction "PMODE0_45") (pintype "passive"))
    )
    (net (code "49") (name "Net-(U6-PMODE1)") (class "Default")
      (node (ref "R17") (pin "2") (pinfunction "2_2") (pintype "passive"))
      (node (ref "U6") (pin "44") (pinfunction "PMODE1_44") (pintype "passive"))
    )
    (net (code "50") (name "Net-(U6-PMODE2)") (class "Default")
      (node (ref "R18") (pin "2") (pinfunction "2_2") (pintype "passive"))
      (node (ref "U6") (pin "43") (pinfunction "PMODE2_43") (pintype "passive"))
    )
    (net (code "51") (name "Net-(U6-TOCAP)") (class "Default")
      (node (ref "C30") (pin "P$2") (pinfunction "P$2_P$2") (pintype "passive"))
      (node (ref "U6") (pin "20") (pinfunction "TOCAP_20") (pintype "passive"))
    )
    (net (code "52") (name "PIO0_1{slash}ISP") (class "Default")
      (node (ref "JP2") (pin "14") (pinfunction "14_14") (pintype "passive"))
      (node (ref "R10") (pin "1") (pinfunction "P$1_1") (pintype "passive"))
      (node (ref "R3") (pin "2") (pinfunction "P$2_2") (pintype "passive"))
      (node (ref "S2") (pin "3") (pinfunction "2.1_3") (pintype "passive"))
      (node (ref "S2") (pin "4") (pinfunction "2.2_4") (pintype "passive"))
      (node (ref "U3") (pin "3") (pinfunction "PIO0_1/CLKOUT/CT32B0_MAT2_3") (pintype "bidirectional"))
    )
    (net (code "53") (name "PIO0_2{slash}SSEL0") (class "Default")
      (node (ref "JP2") (pin "9") (pinfunction "9_9") (pintype "passive"))
      (node (ref "R27") (pin "1") (pinfunction "P$1_1") (pintype "passive"))
      (node (ref "U3") (pin "8") (pinfunction "PIO0_2/SSEL0/CT16B0_CAP0_8") (pintype "bidirectional"))
      (node (ref "U6") (pin "32") (pinfunction "SCS_N_32") (pintype "passive"))
    )
    (net (code "54") (name "PIO0_3{slash}W5500_RST") (class "Default")
      (node (ref "JP2") (pin "7") (pinfunction "7_7") (pintype "passive"))
      (node (ref "R25") (pin "1") (pinfunction "P$1_1") (pintype "passive"))
      (node (ref "U3") (pin "9") (pinfunction "PIO0_3_9") (pintype "bidirectional"))
      (node (ref "U6") (pin "37") (pinfunction "RST_N_37") (pintype "passive"))
    )
    (net (code "55") (name "PIO0_4{slash}SCL") (class "Default")
      (node (ref "$$U$3") (pin "SCL") (pinfunction "SCL_SCL") (pintype "bidirectional"))
      (node (ref "C23") (pin "2") (pinfunction "P$2_2") (pintype "passive"))
      (node (ref "JP1") (pin "1") (pinfunction "1_1") (pintype "passive"))
      (node (ref "R36") (pin "1") (pinfunction "P$1_1") (pintype "passive"))
      (node (ref "S5") (pin "3") (pinfunction "2.1_3") (pintype "passive"))
      (node (ref "S5") (pin "4") (pinfunction "2.2_4") (pintype "passive"))
      (node (ref "U3") (pin "10") (pinfunction "PIO0_4/SCL_10") (pintype "bidirectional"))
    )
    (net (code "56") (name "PIO0_5{slash}SDA") (class "Default")
      (node (ref "$$U$3") (pin "SDA") (pinfunction "SDA_SDA") (pintype "bidirectional"))
      (node (ref "C14") (pin "2") (pinfunction "P$2_2") (pintype "passive"))
      (node (ref "JP1") (pin "2") (pinfunction "2_2") (pintype "passive"))
      (node (ref "R28") (pin "1") (pinfunction "P$1_1") (pintype "passive"))
      (node (ref "S4") (pin "3") (pinfunction "2.1_3") (pintype "passive"))
      (node (ref "S4") (pin "4") (pinfunction "2.2_4") (pintype "passive"))
      (node (ref "U3") (pin "11") (pinfunction "PIO0_5/SDA_11") (pintype "bidirectional"))
    )
    (net (code "57") (name "PIO0_6{slash}SCK0") (class "Default")
      (node (ref "$$U$3") (pin "D13") (pinfunction "D13_D13") (pintype "bidirectional"))
      (node (ref "$$U$3") (pin "SCK") (pinfunction "SCK_SCK") (pintype "passive"))
      (node (ref "JP1") (pin "3") (pinfunction "3_3") (pintype "passive"))
      (node (ref "U3") (pin "15") (pinfunction "PIO0_6/R/SCK0_15") (pintype "bidirectional"))
      (node (ref "U4") (pin "2") (pinfunction "SCK_2") (pintype "passive"))
      (node (ref "U6") (pin "33") (pinfunction "SCLK_33") (pintype "passive"))
    )
    (net (code "58") (name "PIO0_7{slash}INT_N") (class "Default")
      (node (ref "JP2") (pin "8") (pinfunction "8_8") (pintype "passive"))
      (node (ref "R26") (pin "1") (pinfunction "P$1_1") (pintype "passive"))
      (node (ref "U3") (pin "16") (pinfunction "PIO0_7/~{CTS}_16") (pintype "bidirectional"))
      (node (ref "U6") (pin "36") (pinfunction "INT_N_36") (pintype "passive"))
    )
    (net (code "59") (name "PIO0_8{slash}MISO0") (class "Default")
      (node (ref "$$U$3") (pin "D12") (pinfunction "D12_D12") (pintype "bidirectional"))
      (node (ref "$$U$3") (pin "MISO") (pinfunction "MISO_MISO") (pintype "passive"))
      (node (ref "JP1") (pin "4") (pinfunction "4_4") (pintype "passive"))
      (node (ref "U3") (pin "17") (pinfunction "PIO0_8/MISO0/CT16B0_MAT0_17") (pintype "bidirectional"))
      (node (ref "U4") (pin "8") (pinfunction "SO_8") (pintype "passive"))
      (node (ref "U6") (pin "34") (pinfunction "MISO_34") (pintype "passive"))
    )
    (net (code "60") (name "PIO0_9{slash}MOSI0") (class "Default")
      (node (ref "$$U$3") (pin "D11") (pinfunction "D11_D11") (pintype "bidirectional"))
      (node (ref "$$U$3") (pin "MOSI") (pinfunction "MOSI_MOSI") (pintype "passive"))
      (node (ref "JP1") (pin "5") (pinfunction "5_5") (pintype "passive"))
      (node (ref "U3") (pin "18") (pinfunction "PIO0_9/MOSI0/CT16B0_MAT1/SWO_18") (pintype "bidirectional"))
      (node (ref "U4") (pin "1") (pinfunction "SI_1") (pintype "passive"))
      (node (ref "U6") (pin "35") (pinfunction "MOSI_35") (pintype "passive"))
    )
    (net (code "61") (name "PIO0_11{slash}AD0") (class "Default")
      (node (ref "JP2") (pin "11") (pinfunction "11_11") (pintype "passive"))
      (node (ref "S6") (pin "1") (pinfunction "1_1") (pintype "passive"))
      (node (ref "U3") (pin "21") (pinfunction "TDI/PIO0_11/AD0/CT32B0_MAT3_21") (pintype "bidirectional"))
    )
    (net (code "62") (name "PIO0_12{slash}AD1") (class "Default")
      (node (ref "$$U$3") (pin "A1") (pinfunction "A1_A1") (pintype "bidirectional"))
      (node (ref "JP2") (pin "12") (pinfunction "12_12") (pintype "passive"))
      (node (ref "U3") (pin "22") (pinfunction "TMS/PIO0_12/AD1/CT32B1_CAP0_22") (pintype "bidirectional"))
    )
    (net (code "63") (name "PIO0_13{slash}AD2") (class "Default")
      (node (ref "$$U$3") (pin "A2") (pinfunction "A2_A2") (pintype "bidirectional"))
      (node (ref "JP2") (pin "13") (pinfunction "13_13") (pintype "passive"))
      (node (ref "U3") (pin "23") (pinfunction "TDO/PIO0_13/AD2/CT32B1_MAT0_23") (pintype "bidirectional"))
    )
    (net (code "64") (name "PIO0_14{slash}AD3") (class "Default")
      (node (ref "$$U$3") (pin "A3") (pinfunction "A3_A3") (pintype "bidirectional"))
      (node (ref "$$U$3") (pin "D4") (pinfunction "D4_D4") (pintype "bidirectional"))
      (node (ref "JP1") (pin "12") (pinfunction "12_12") (pintype "passive"))
      (node (ref "U3") (pin "24") (pinfunction "~{TRST}/PIO0_14/AD3/CT32B1_MAT1_24") (pintype "bidirectional"))
    )
    (net (code "65") (name "PIO0_16{slash}AD5") (class "Default")
      (node (ref "$$U$3") (pin "A4") (pinfunction "A4_A4") (pintype "bidirectional"))
      (node (ref "$$U$3") (pin "D5") (pinfunction "D5_D5") (pintype "bidirectional"))
      (node (ref "JP1") (pin "11") (pinfunction "11_11") (pintype "passive"))
      (node (ref "U3") (pin "26") (pinfunction "PIO0_16/AD5/CT32B1_MAT3/WAKEUP_26") (pintype "bidirectional"))
    )
    (net (code "66") (name "PIO0_17") (class "Default")
      (node (ref "$$U$3") (pin "D3") (pinfunction "D3_D3") (pintype "bidirectional"))
      (node (ref "JP1") (pin "13") (pinfunction "13_13") (pintype "passive"))
      (node (ref "U3") (pin "30") (pinfunction "PIO0_17/~{RTS}/CT32B0_CAP0_30") (pintype "bidirectional"))
    )
    (net (code "67") (name "PIO0_18{slash}RXD") (class "Default")
      (node (ref "JP1") (pin "16") (pinfunction "16_16") (pintype "passive"))
      (node (ref "R12") (pin "1") (pinfunction "P$1_1") (pintype "passive"))
      (node (ref "R23") (pin "2") (pinfunction "P$2_2") (pintype "passive"))
      (node (ref "U3") (pin "31") (pinfunction "PIO0_18/RXD/CT32B0_MAT0_31") (pintype "bidirectional"))
    )
    (net (code "68") (name "PIO0_19{slash}TXD") (class "Default")
      (node (ref "JP1") (pin "15") (pinfunction "15_15") (pintype "passive"))
      (node (ref "R11") (pin "1") (pinfunction "P$1_1") (pintype "passive"))
      (node (ref "R9") (pin "2") (pinfunction "P$2_2") (pintype "passive"))
      (node (ref "U3") (pin "32") (pinfunction "PIO0_19/TXD/CT32B0_MAT1_32") (pintype "bidirectional"))
    )
    (net (code "69") (name "PIO0_20") (class "Default")
      (node (ref "$$U$3") (pin "D7") (pinfunction "D7_D7") (pintype "bidirectional"))
      (node (ref "JP1") (pin "9") (pinfunction "9_9") (pintype "passive"))
      (node (ref "U3") (pin "7") (pinfunction "PIO0_20/CT16B1_CAP0_7") (pintype "bidirectional"))
    )
    (net (code "70") (name "PIO0_22{slash}AD6") (class "Default")
      (node (ref "$$U$3") (pin "A0") (pinfunction "A0_A0") (pintype "bidirectional"))
      (node (ref "JP2") (pin "10") (pinfunction "10_10") (pintype "passive"))
      (node (ref "U3") (pin "20") (pinfunction "PIO0_22/AD6/CT16B1_MAT1/MISO1_20") (pintype "bidirectional"))
    )
    (net (code "71") (name "PIO0_23{slash}AD7") (class "Default")
      (node (ref "$$U$3") (pin "A5") (pinfunction "A5_A5") (pintype "bidirectional"))
      (node (ref "$$U$3") (pin "D6") (pinfunction "D6_D6") (pintype "bidirectional"))
      (node (ref "JP1") (pin "10") (pinfunction "10_10") (pintype "passive"))
      (node (ref "U3") (pin "27") (pinfunction "PIO0_23/AD7_27") (pintype "bidirectional"))
    )
    (net (code "72") (name "PIO1_15") (class "Default")
      (node (ref "$$U$3") (pin "D2") (pinfunction "D2_D2") (pintype "bidirectional"))
      (node (ref "JP1") (pin "14") (pinfunction "14_14") (pintype "passive"))
      (node (ref "U3") (pin "28") (pinfunction "PIO1_15/~{DCD}/CT16B0_MAT2/SCK1_28") (pintype "bidirectional"))
    )
    (net (code "73") (name "PIO1_19{slash}SSEL1") (class "Default")
      (node (ref "JP1") (pin "17") (pinfunction "17_17") (pintype "passive"))
      (node (ref "U3") (pin "1") (pinfunction "PIO1_19/~{DTR}/SSEL1_1") (pintype "bidirectional"))
      (node (ref "U4") (pin "4") (pinfunction "~{CS}_4") (pintype "passive"))
    )
    (net (code "74") (name "PIO1_21{slash}LEDR") (class "Default")
      (node (ref "$$U$3") (pin "D8") (pinfunction "D8_D8") (pintype "bidirectional"))
      (node (ref "JP1") (pin "8") (pinfunction "8_8") (pintype "passive"))
      (node (ref "R5") (pin "1") (pinfunction "P$1_1") (pintype "passive"))
      (node (ref "U3") (pin "12") (pinfunction "PIO0_21/CT16B1_MAT0/MOSI1_12") (pintype "bidirectional"))
    )
    (net (code "75") (name "PIO1_23{slash}LEDG") (class "Default")
      (node (ref "$$U$3") (pin "D9") (pinfunction "D9_D9") (pintype "bidirectional"))
      (node (ref "JP1") (pin "7") (pinfunction "7_7") (pintype "passive"))
      (node (ref "R6") (pin "1") (pinfunction "P$1_1") (pintype "passive"))
      (node (ref "U3") (pin "13") (pinfunction "PIO1_23/CT16B1_MAT1/SSEL1_13") (pintype "bidirectional"))
    )
    (net (code "76") (name "PIO1_24{slash}LEDB") (class "Default")
      (node (ref "$$U$3") (pin "D10") (pinfunction "D10_D10") (pintype "bidirectional"))
      (node (ref "JP1") (pin "6") (pinfunction "6_6") (pintype "passive"))
      (node (ref "R4") (pin "1") (pinfunction "P$1_1") (pintype "passive"))
      (node (ref "U3") (pin "14") (pinfunction "PIO1_24/CT32B0_MAT0_14") (pintype "bidirectional"))
    )
    (net (code "77") (name "RXN") (class "Default")
      (node (ref "C25") (pin "2") (pinfunction "P$2_2") (pintype "passive"))
      (node (ref "R33") (pin "2") (pinfunction "P$2_2") (pintype "passive"))
      (node (ref "U6") (pin "5") (pinfunction "RXN_5") (pintype "passive"))
    )
    (net (code "78") (name "RXP") (class "Default")
      (node (ref "C18") (pin "2") (pinfunction "P$2_2") (pintype "passive"))
      (node (ref "R32") (pin "2") (pinfunction "P$2_2") (pintype "passive"))
      (node (ref "U6") (pin "6") (pinfunction "RXP_6") (pintype "passive"))
    )
    (net (code "79") (name "SWCLK{slash}PIO0_10") (class "Default")
      (node (ref "J2") (pin "4") (pinfunction "4_4") (pintype "passive"))
      (node (ref "JP2") (pin "16") (pinfunction "16_16") (pintype "passive"))
      (node (ref "U3") (pin "19") (pinfunction "SWCLK/PIO0_10/SCK0/CT16B0_MAT2_19") (pintype "bidirectional"))
    )
    (net (code "80") (name "SWDIO{slash}PIO0_15") (class "Default")
      (node (ref "J2") (pin "2") (pinfunction "2_2") (pintype "passive"))
      (node (ref "JP2") (pin "15") (pinfunction "15_15") (pintype "passive"))
      (node (ref "U3") (pin "25") (pinfunction "SWDIO/PIO0_15/AD4/CT32B1_MAT2_25") (pintype "bidirectional"))
    )
    (net (code "81") (name "TXN") (class "Default")
      (node (ref "P1") (pin "3") (pinfunction "TD-_3") (pintype "passive"))
      (node (ref "R31") (pin "1") (pinfunction "P$1_1") (pintype "passive"))
      (node (ref "U6") (pin "1") (pinfunction "TXN_1") (pintype "passive"))
    )
    (net (code "82") (name "TXP") (class "Default")
      (node (ref "P1") (pin "1") (pinfunction "TD+_1") (pintype "passive"))
      (node (ref "R29") (pin "1") (pinfunction "P$1_1") (pintype "passive"))
      (node (ref "U6") (pin "2") (pinfunction "TXP_2") (pintype "passive"))
    )
    (net (code "83") (name "VCCIO") (class "Default")
      (node (ref "C2") (pin "2") (pinfunction "P$2_2") (pintype "passive"))
      (node (ref "LED3") (pin "1") (pinfunction "P$1_1") (pintype "bidirectional"))
      (node (ref "LED4") (pin "1") (pinfunction "P$1_1") (pintype "bidirectional"))
      (node (ref "U2") (pin "17") (pinfunction "3V3OUT_17") (pintype "output"))
      (node (ref "U2") (pin "19") (pinfunction "~{RESET}_19") (pintype "input"))
      (node (ref "U2") (pin "4") (pinfunction "VCCIO_4") (pintype "power_in"))
    )
    (net (code "84") (name "VCC{slash}2") (class "Default")
      (node (ref "C12") (pin "1") (pinfunction "1_1") (pintype "passive"))
      (node (ref "C4") (pin "2") (pinfunction "P$2_2") (pintype "passive"))
      (node (ref "D2") (pin "2") (pinfunction "2_2") (pintype "bidirectional"))
      (node (ref "L1") (pin "2") (pinfunction "2_2") (pintype "passive"))
      (node (ref "TP1") (pin "TP") (pinfunction "TP_TP") (pintype "input"))
      (node (ref "U2") (pin "20") (pinfunction "VCC_20") (pintype "power_in"))
    )
    (net (code "85") (name "VIN") (class "Default")
      (node (ref "$$U$3") (pin "VIN") (pinfunction "VIN_VIN") (pintype "power_in"))
    )
    (net (code "86") (name "unconnected-($$U$3-PadRESERVED)") (class "Default")
      (node (ref "$$U$3") (pin "RESERVED") (pinfunction "RESERVED_RESERVED") (pintype "no_connect"))
    )
    (net (code "87") (name "unconnected-(J2-Pad6)") (class "Default")
      (node (ref "J2") (pin "6") (pinfunction "6_6") (pintype "passive"))
    )
    (net (code "88") (name "unconnected-(J2-Pad8)") (class "Default")
      (node (ref "J2") (pin "8") (pinfunction "8_8") (pintype "passive"))
    )
    (net (code "89") (name "unconnected-(P1-NC-Pad7)") (class "Default")
      (node (ref "P1") (pin "7") (pinfunction "NC_7") (pintype "passive"))
    )
    (net (code "90") (name "unconnected-(S1-Pad3)") (class "Default")
      (node (ref "S1") (pin "3") (pinfunction "3_3") (pintype "passive"))
    )
    (net (code "91") (name "unconnected-(U2-CBUS2-Pad13)") (class "Default")
      (node (ref "U2") (pin "13") (pinfunction "CBUS2_13") (pintype "bidirectional"))
    )
    (net (code "92") (name "unconnected-(U2-CBUS3-Pad14)") (class "Default")
      (node (ref "U2") (pin "14") (pinfunction "CBUS3_14") (pintype "bidirectional"))
    )
    (net (code "93") (name "unconnected-(U2-CBUS4-Pad12)") (class "Default")
      (node (ref "U2") (pin "12") (pinfunction "CBUS4_12") (pintype "bidirectional"))
    )
    (net (code "94") (name "unconnected-(U2-OSCI-Pad27)") (class "Default")
      (node (ref "U2") (pin "27") (pinfunction "OSCI_27") (pintype "input"))
    )
    (net (code "95") (name "unconnected-(U2-OSCO-Pad28)") (class "Default")
      (node (ref "U2") (pin "28") (pinfunction "OSCO_28") (pintype "output"))
    )
    (net (code "96") (name "unconnected-(U2-~{CTS}-Pad11)") (class "Default")
      (node (ref "U2") (pin "11") (pinfunction "~{CTS}_11") (pintype "input"))
    )
    (net (code "97") (name "unconnected-(U2-~{DCD}-Pad10)") (class "Default")
      (node (ref "U2") (pin "10") (pinfunction "~{DCD}_10") (pintype "input"))
    )
    (net (code "98") (name "unconnected-(U2-~{DSR}-Pad9)") (class "Default")
      (node (ref "U2") (pin "9") (pinfunction "~{DSR}_9") (pintype "input"))
    )
    (net (code "99") (name "unconnected-(U2-~{DTR}-Pad2)") (class "Default")
      (node (ref "U2") (pin "2") (pinfunction "~{DTR}_2") (pintype "output"))
    )
    (net (code "100") (name "unconnected-(U2-~{RI}-Pad6)") (class "Default")
      (node (ref "U2") (pin "6") (pinfunction "~{RI}_6") (pintype "input"))
    )
    (net (code "101") (name "unconnected-(U2-~{RTS}-Pad3)") (class "Default")
      (node (ref "U2") (pin "3") (pinfunction "~{RTS}_3") (pintype "output"))
    )
    (net (code "102") (name "unconnected-(U6-DNC-Pad7)") (class "Default")
      (node (ref "U6") (pin "7") (pinfunction "DNC_7") (pintype "passive"))
    )
    (net (code "103") (name "unconnected-(U6-DUPLED-Pad26)") (class "Default")
      (node (ref "U6") (pin "26") (pinfunction "DUPLED_26") (pintype "passive"))
    )
    (net (code "104") (name "unconnected-(U6-NC-Pad12)") (class "Default")
      (node (ref "U6") (pin "12") (pinfunction "NC_12") (pintype "passive"))
    )
    (net (code "105") (name "unconnected-(U6-NC-Pad13)") (class "Default")
      (node (ref "U6") (pin "13") (pinfunction "NC_13") (pintype "passive"))
    )
    (net (code "106") (name "unconnected-(U6-NC-Pad46)") (class "Default")
      (node (ref "U6") (pin "46") (pinfunction "NC_46") (pintype "passive"))
    )
    (net (code "107") (name "unconnected-(U6-NC-Pad47)") (class "Default")
      (node (ref "U6") (pin "47") (pinfunction "NC_47") (pintype "passive"))
    )
    (net (code "108") (name "unconnected-(U6-SPDLED-Pad24)") (class "Default")
      (node (ref "U6") (pin "24") (pinfunction "SPDLED_24") (pintype "passive"))
    )
    (net (code "109") (name "unconnected-(U6-VBG-Pad18)") (class "Default")
      (node (ref "U6") (pin "18") (pinfunction "VBG_18") (pintype "passive"))
    )
    (net (code "110") (name "unconnected-(X1-Pad4)") (class "Default")
      (node (ref "X1") (pin "4") (pinfunction "4_4") (pintype "passive"))
    )
    (net (code "111") (name "unconnected-(Y1-Pad2)") (class "Default")
      (node (ref "Y1") (pin "2") (pinfunction "2_2") (pintype "passive"))
    )
    (net (code "112") (name "unconnected-(Y1-Pad4)") (class "Default")
      (node (ref "Y1") (pin "4") (pinfunction "4_4") (pintype "passive"))
    )
    (net (code "113") (name "unconnected-(Y2-Pad2)") (class "Default")
      (node (ref "Y2") (pin "2") (pinfunction "2_2") (pintype "passive"))
    )
    (net (code "114") (name "unconnected-(Y2-Pad4)") (class "Default")
      (node (ref "Y2") (pin "4") (pinfunction "4_4") (pintype "passive"))
    )
    (net (code "115") (name "~{RESET}{slash}PIO0_0") (class "Default")
      (node (ref "$$U$3") (pin "RESET") (pinfunction "/RESET_RESET") (pintype "bidirectional"))
      (node (ref "$$U$3") (pin "RESET_ICSP") (pinfunction "RST_RESET_ICSP") (pintype "passive"))
      (node (ref "C10") (pin "2") (pinfunction "P$2_2") (pintype "passive"))
      (node (ref "J2") (pin "10") (pinfunction "10_10") (pintype "passive"))
      (node (ref "JP2") (pin "17") (pinfunction "17_17") (pintype "passive"))
      (node (ref "R13") (pin "1") (pinfunction "P$1_1") (pintype "passive"))
      (node (ref "S3") (pin "3") (pinfunction "2.1_3") (pintype "passive"))
      (node (ref "S3") (pin "4") (pinfunction "2.2_4") (pintype "passive"))
      (node (ref "U3") (pin "2") (pinfunction "~{RESET}/PIO0_0_2") (pintype "bidirectional"))
      (node (ref "U4") (pin "3") (pinfunction "~{RESET}_3") (pintype "passive"))
    )
  )
)
